# Circuito_de_Aplicacion_Ej4.net
KiCad netlist of a schematic drawn in Altium Designer
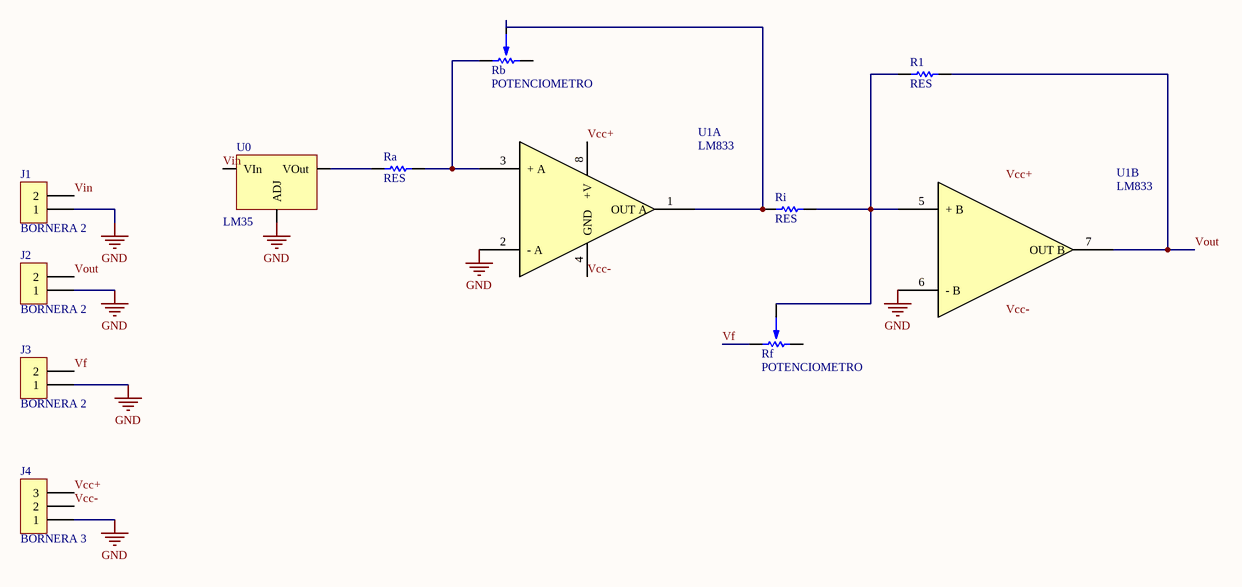
[diagram p0: Circuito de Aplicacion Ej4.SchDoc]

(export (version "E")
  (design (tool "Eeschema 10.0.6"))
  (components
    (comp (ref "J1")
      (value "BORNERA 2")
      (footprint "BORNERA2")
      (libsource (lib "LIBEBAL") (part "BORNERA 2"))
    )
    (comp (ref "J2")
      (value "BORNERA 2")
      (footprint "BORNERA2")
      (libsource (lib "LIBEBAL") (part "BORNERA 2"))
    )
    (comp (ref "J3")
      (value "BORNERA 2")
      (footprint "BORNERA2")
      (libsource (lib "LIBEBAL") (part "BORNERA 2"))
    )
    (comp (ref "J4")
      (value "BORNERA 3")
      (footprint "BORNERA3")
      (libsource (lib "LIBEBAL") (part "BORNERA 3"))
    )
    (comp (ref "R1") (value "RES") (footprint "RES400") (libsource (lib "LIBEBAL") (part "RES")))
    (comp (ref "Ra") (value "RES") (footprint "RES400") (libsource (lib "LIBEBAL") (part "RES")))
    (comp (ref "Rb")
      (value "POTENCIOMETRO")
      (footprint "POTENCIOMETRO")
      (libsource (lib "LIBEBAL") (part "POTENCIOMETRO"))
    )
    (comp (ref "Rf")
      (value "POTENCIOMETRO")
      (footprint "POTENCIOMETRO")
      (libsource (lib "LIBEBAL") (part "POTENCIOMETRO"))
    )
    (comp (ref "Ri") (value "RES") (footprint "RES400") (libsource (lib "LIBEBAL") (part "RES")))
    (comp (ref "U0")
      (value "LM35")
      (footprint "TO-220 H - DISIPADOR")
      (description "IC REG ADJ 1.5A 3 TERM TO-220")
      (libsource (lib "LIBEBAL") (part "LM317"))
    )
    (comp (ref "U1")
      (value "LM833")
      (footprint "DIP8")
      (description "Dual Audio Operational Amplifier")
      (libsource (lib "LIBEBAL") (part "LM833"))
    )
  )
  (nets
    (net (code "1") (name "/Vcc+") (class "Default")
      (node (ref "J4") (pin "3") (pinfunction "3_3") (pintype "passive"))
      (node (ref "U1") (pin "8") (pinfunction "+V_8") (pintype "passive"))
    )
    (net (code "2") (name "/Vcc-") (class "Default")
      (node (ref "J4") (pin "2") (pinfunction "2_2") (pintype "passive"))
      (node (ref "U1") (pin "4") (pinfunction "GND_4") (pintype "passive"))
    )
    (net (code "3") (name "/Vf") (class "Default")
      (node (ref "J3") (pin "2") (pinfunction "2_2") (pintype "passive"))
      (node (ref "Rf") (pin "1") (pinfunction "1_1") (pintype "passive"))
    )
    (net (code "4") (name "/Vin") (class "Default")
      (node (ref "J1") (pin "2") (pinfunction "2_2") (pintype "passive"))
      (node (ref "U0") (pin "3") (pinfunction "VIn_3") (pintype "passive"))
    )
    (net (code "5") (name "/Vout") (class "Default")
      (node (ref "J2") (pin "2") (pinfunction "2_2") (pintype "passive"))
      (node (ref "R1") (pin "2") (pinfunction "2_2") (pintype "passive"))
      (node (ref "U1") (pin "7") (pinfunction "OUT_B_7") (pintype "passive"))
    )
    (net (code "6") (name "GND") (class "Default")
      (node (ref "J1") (pin "1") (pinfunction "1_1") (pintype "passive"))
      (node (ref "J2") (pin "1") (pinfunction "1_1") (pintype "passive"))
      (node (ref "J3") (pin "1") (pinfunction "1_1") (pintype "passive"))
      (node (ref "J4") (pin "1") (pinfunction "1_1") (pintype "passive"))
      (node (ref "U0") (pin "1") (pinfunction "ADJ_1") (pintype "passive"))
      (node (ref "U1") (pin "2") (pinfunction "-_A_2") (pintype "passive"))
      (node (ref "U1") (pin "6") (pinfunction "-_B_6") (pintype "passive"))
    )
    (net (code "7") (name "Net-(U0-VOut)") (class "Default")
      (node (ref "Ra") (pin "1") (pinfunction "1_1") (pintype "passive"))
      (node (ref "U0") (pin "2") (pinfunction "VOut_2") (pintype "passive"))
    )
    (net (code "8") (name "Net-(U1A-+_A)") (class "Default")
      (node (ref "Ra") (pin "2") (pinfunction "2_2") (pintype "passive"))
      (node (ref "Rb") (pin "1") (pinfunction "1_1") (pintype "passive"))
      (node (ref "U1") (pin "3") (pinfunction "+_A_3") (pintype "passive"))
    )
    (net (code "9") (name "Net-(U1A-OUT_A)") (class "Default")
      (node (ref "Rb") (pin "2") (pinfunction "2_2") (pintype "passive"))
      (node (ref "Ri") (pin "1") (pinfunction "1_1") (pintype "passive"))
      (node (ref "U1") (pin "1") (pinfunction "OUT_A_1") (pintype "passive"))
    )
    (net (code "10") (name "Net-(U1B-+_B)") (class "Default")
      (node (ref "R1") (pin "1") (pinfunction "1_1") (pintype "passive"))
      (node (ref "Rf") (pin "2") (pinfunction "2_2") (pintype "passive"))
      (node (ref "Ri") (pin "2") (pinfunction "2_2") (pintype "passive"))
      (node (ref "U1") (pin "5") (pinfunction "+_B_5") (pintype "passive"))
    )
    (net (code "11") (name "unconnected-(Rb-Pad3)") (class "Default")
      (node (ref "Rb") (pin "3") (pinfunction "3_3") (pintype "passive"))
    )
    (net (code "12") (name "unconnected-(Rf-Pad3)") (class "Default")
      (node (ref "Rf") (pin "3") (pinfunction "3_3") (pintype "passive"))
    )
  )
)
